# pokey-synth.net
KiCad netlist of a schematic drawn in EAGLE
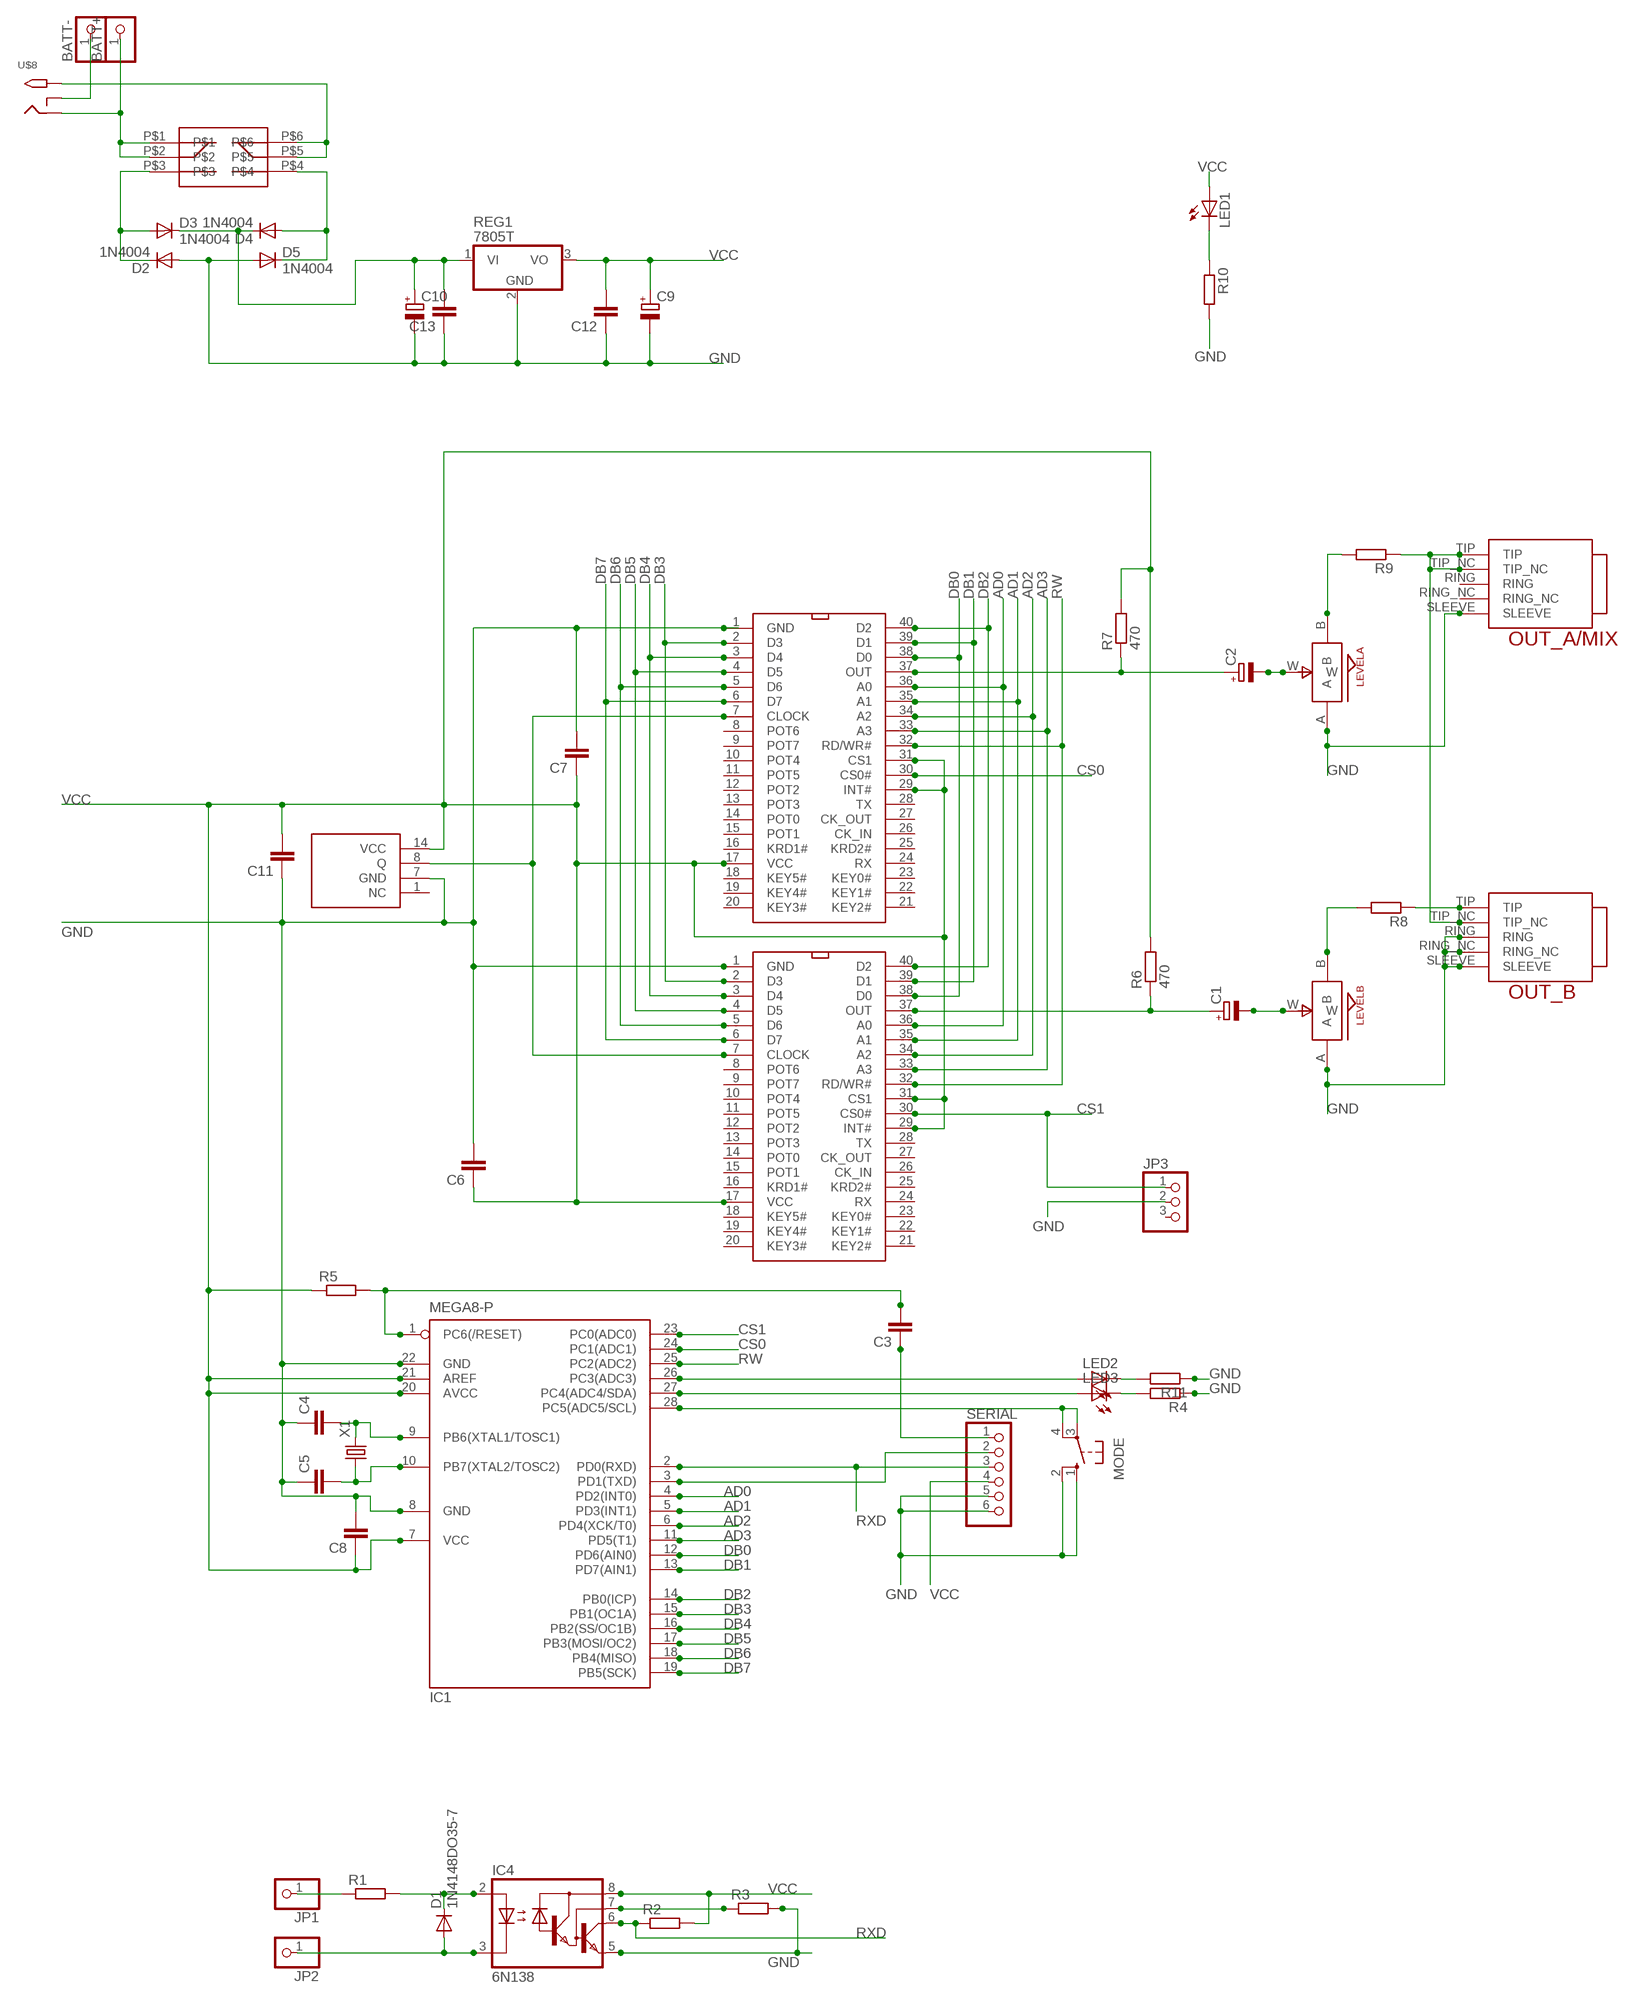
[diagram p0: schematic, sheet 1]

(export (version "E")
  (design (tool "Eeschema 10.0.6"))
  (components
    (comp (ref "BATT+")
      (value "PINHD-1X1")
      (footprint "eagle-import:1X01")
      (libsource (lib "eagle-import") (part "PINHD-1X1"))
    )
    (comp (ref "BATT-")
      (value "PINHD-1X1")
      (footprint "eagle-import:1X01")
      (libsource (lib "eagle-import") (part "PINHD-1X1"))
    )
    (comp (ref "C1")
      (value "CPOL-EUE2-5")
      (footprint "eagle-import:E2-5")
      (libsource (lib "eagle-import") (part "CPOL-EUE2-5"))
    )
    (comp (ref "C2")
      (value "CPOL-EUE2-5")
      (footprint "eagle-import:E2-5")
      (libsource (lib "eagle-import") (part "CPOL-EUE2-5"))
    )
    (comp (ref "C3")
      (value "C-EU025-024X044")
      (footprint "eagle-import:C025-024X044")
      (libsource (lib "eagle-import") (part "C-EU025-024X044"))
    )
    (comp (ref "C4")
      (value "C-EU025-024X044")
      (footprint "eagle-import:C025-024X044")
      (libsource (lib "eagle-import") (part "C-EU025-024X044"))
    )
    (comp (ref "C5")
      (value "C-EU025-024X044")
      (footprint "eagle-import:C025-024X044")
      (libsource (lib "eagle-import") (part "C-EU025-024X044"))
    )
    (comp (ref "C6")
      (value "C-EU025-024X044")
      (footprint "eagle-import:C025-024X044")
      (libsource (lib "eagle-import") (part "C-EU025-024X044"))
    )
    (comp (ref "C7")
      (value "C-EU025-024X044")
      (footprint "eagle-import:C025-024X044")
      (libsource (lib "eagle-import") (part "C-EU025-024X044"))
    )
    (comp (ref "C8")
      (value "C-EU025-024X044")
      (footprint "eagle-import:C025-024X044")
      (libsource (lib "eagle-import") (part "C-EU025-024X044"))
    )
    (comp (ref "C9")
      (value "CPOL-EUE2-5")
      (footprint "eagle-import:E2-5")
      (libsource (lib "eagle-import") (part "CPOL-EUE2-5"))
    )
    (comp (ref "C10")
      (value "CPOL-EUE2-5")
      (footprint "eagle-import:E2-5")
      (libsource (lib "eagle-import") (part "CPOL-EUE2-5"))
    )
    (comp (ref "C11")
      (value "C-EU025-024X044")
      (footprint "eagle-import:C025-024X044")
      (libsource (lib "eagle-import") (part "C-EU025-024X044"))
    )
    (comp (ref "C12")
      (value "C-EU025-024X044")
      (footprint "eagle-import:C025-024X044")
      (libsource (lib "eagle-import") (part "C-EU025-024X044"))
    )
    (comp (ref "C13")
      (value "C-EU025-024X044")
      (footprint "eagle-import:C025-024X044")
      (libsource (lib "eagle-import") (part "C-EU025-024X044"))
    )
    (comp (ref "D1")
      (value "1N4148DO35-7")
      (footprint "eagle-import:DO35-7")
      (libsource (lib "eagle-import") (part "1N4148DO35-7"))
    )
    (comp (ref "D2")
      (value "1N4004")
      (footprint "eagle-import:DO-VERT")
      (libsource (lib "eagle-import") (part "1N4004"))
    )
    (comp (ref "D3")
      (value "1N4004")
      (footprint "eagle-import:DO-VERT")
      (libsource (lib "eagle-import") (part "1N4004"))
    )
    (comp (ref "D4")
      (value "1N4004")
      (footprint "eagle-import:DO-VERT")
      (libsource (lib "eagle-import") (part "1N4004"))
    )
    (comp (ref "D5")
      (value "1N4004")
      (footprint "eagle-import:DO-VERT")
      (libsource (lib "eagle-import") (part "1N4004"))
    )
    (comp (ref "IC1")
      (value "MEGA8-P")
      (footprint "eagle-import:DIL28-3")
      (libsource (lib "eagle-import") (part "MEGA8-P"))
    )
    (comp (ref "IC2")
      (value "POKEYDIP40")
      (footprint "eagle-import:DIL40")
      (libsource (lib "eagle-import") (part "POKEYDIP40"))
    )
    (comp (ref "IC3")
      (value "POKEYDIP40")
      (footprint "eagle-import:DIL40")
      (libsource (lib "eagle-import") (part "POKEYDIP40"))
    )
    (comp (ref "IC4")
      (value "6N138")
      (footprint "eagle-import:DIL08")
      (fields (field (name "MF") "VISHAY/TELEFUNKEN"))
      (libsource (lib "eagle-import") (part "6N138"))
    )
    (comp (ref "JP1")
      (value "PINHD-1X1")
      (footprint "eagle-import:1X01")
      (libsource (lib "eagle-import") (part "PINHD-1X1"))
    )
    (comp (ref "JP2")
      (value "PINHD-1X1")
      (footprint "eagle-import:1X01")
      (libsource (lib "eagle-import") (part "PINHD-1X1"))
    )
    (comp (ref "JP3")
      (value "PINHD-1X3")
      (footprint "eagle-import:1X03")
      (libsource (lib "eagle-import") (part "PINHD-1X3"))
    )
    (comp (ref "LED1")
      (value "LED3MM")
      (footprint "eagle-import:LED3MM")
      (libsource (lib "eagle-import") (part "LED3MM"))
    )
    (comp (ref "LED2")
      (value "LED3MM")
      (footprint "eagle-import:LED3MM")
      (libsource (lib "eagle-import") (part "LED3MM"))
    )
    (comp (ref "LED3")
      (value "LED3MM")
      (footprint "eagle-import:LED3MM")
      (libsource (lib "eagle-import") (part "LED3MM"))
    )
    (comp (ref "LEVELA")
      (value "ALPS_POT_SMALL")
      (footprint "eagle-import:SMALL_ALPS_POT")
      (libsource (lib "eagle-import") (part "ALPS_POT_SMALL"))
    )
    (comp (ref "LEVELB")
      (value "ALPS_POT_SMALL")
      (footprint "eagle-import:SMALL_ALPS_POT")
      (libsource (lib "eagle-import") (part "ALPS_POT_SMALL"))
    )
    (comp (ref "MODE")
      (value "10-XX")
      (footprint "eagle-import:B3F-10XX")
      (fields (field (name "MPN") "B3F-1000"))
      (libsource (lib "eagle-import") (part "10-XX"))
    )
    (comp (ref "OSC1")
      (value "TTLOSC")
      (footprint "eagle-import:TTLOSC")
      (libsource (lib "eagle-import") (part "TTLOSC"))
    )
    (comp (ref "OUT_A/MIX")
      (value "TRUCONNECTJACK")
      (footprint "eagle-import:TRUCONNECTJACK")
      (libsource (lib "eagle-import") (part "TRUCONNECTJACK"))
    )
    (comp (ref "OUT_B")
      (value "TRUCONNECTJACK")
      (footprint "eagle-import:TRUCONNECTJACK")
      (libsource (lib "eagle-import") (part "TRUCONNECTJACK"))
    )
    (comp (ref "R1")
      (value "R-EU_0207/7")
      (footprint "eagle-import:0207_7")
      (libsource (lib "eagle-import") (part "R-EU_0207/7"))
    )
    (comp (ref "R2")
      (value "R-EU_0207/7")
      (footprint "eagle-import:0207_7")
      (libsource (lib "eagle-import") (part "R-EU_0207/7"))
    )
    (comp (ref "R3")
      (value "R-EU_0207/7")
      (footprint "eagle-import:0207_7")
      (libsource (lib "eagle-import") (part "R-EU_0207/7"))
    )
    (comp (ref "R4")
      (value "R-EU_0207/7")
      (footprint "eagle-import:0207_7")
      (libsource (lib "eagle-import") (part "R-EU_0207/7"))
    )
    (comp (ref "R5")
      (value "R-EU_0207/7")
      (footprint "eagle-import:0207_7")
      (libsource (lib "eagle-import") (part "R-EU_0207/7"))
    )
    (comp (ref "R6")
      (value "470")
      (footprint "eagle-import:0207_7")
      (libsource (lib "eagle-import") (part "R-EU_0207/7"))
    )
    (comp (ref "R7")
      (value "470")
      (footprint "eagle-import:0207_7")
      (libsource (lib "eagle-import") (part "R-EU_0207/7"))
    )
    (comp (ref "R8")
      (value "R-EU_0207/7")
      (footprint "eagle-import:0207_7")
      (libsource (lib "eagle-import") (part "R-EU_0207/7"))
    )
    (comp (ref "R9")
      (value "R-EU_0207/7")
      (footprint "eagle-import:0207_7")
      (libsource (lib "eagle-import") (part "R-EU_0207/7"))
    )
    (comp (ref "R10")
      (value "R-EU_0207/7")
      (footprint "eagle-import:0207_7")
      (libsource (lib "eagle-import") (part "R-EU_0207/7"))
    )
    (comp (ref "R11")
      (value "R-EU_0207/7")
      (footprint "eagle-import:0207_7")
      (libsource (lib "eagle-import") (part "R-EU_0207/7"))
    )
    (comp (ref "REG1")
      (value "7805T")
      (footprint "eagle-import:TO220H")
      (libsource (lib "eagle-import") (part "78T05"))
    )
    (comp (ref "SERIAL")
      (value "HEADER-1X6")
      (footprint "eagle-import:1X06_OVAL")
      (libsource (lib "eagle-import") (part "HEADER-1X6"))
    )
    (comp (ref "U$8")
      (value "2.1MMJACKTHM")
      (footprint "eagle-import:PJ-102A")
      (libsource (lib "eagle-import") (part "2.1MMJACKTHM"))
    )
    (comp (ref "U$9")
      (value "2P2T_LATCHING")
      (footprint "eagle-import:2P2T_LATCHING")
      (libsource (lib "eagle-import") (part "2P2T_LATCHING"))
    )
    (comp (ref "X1")
      (value "CRYSTALHC49U-V")
      (footprint "eagle-import:HC49U-V")
      (libsource (lib "eagle-import") (part "CRYSTALHC49U-V"))
    )
  )
  (nets
    (net (code "1") (name "/AD0") (class "Default")
      (node (ref "IC1") (pin "4") (pinfunction "PD2(INT0)_4") (pintype "bidirectional"))
      (node (ref "IC2") (pin "36") (pinfunction "A0_36") (pintype "input"))
      (node (ref "IC3") (pin "36") (pinfunction "A0_36") (pintype "input"))
    )
    (net (code "2") (name "/AD1") (class "Default")
      (node (ref "IC1") (pin "5") (pinfunction "PD3(INT1)_5") (pintype "bidirectional"))
      (node (ref "IC2") (pin "35") (pinfunction "A1_35") (pintype "input"))
      (node (ref "IC3") (pin "35") (pinfunction "A1_35") (pintype "input"))
    )
    (net (code "3") (name "/AD2") (class "Default")
      (node (ref "IC1") (pin "6") (pinfunction "PD4(XCK/T0)_6") (pintype "bidirectional"))
      (node (ref "IC2") (pin "34") (pinfunction "A2_34") (pintype "input"))
      (node (ref "IC3") (pin "34") (pinfunction "A2_34") (pintype "input"))
    )
    (net (code "4") (name "/AD3") (class "Default")
      (node (ref "IC1") (pin "11") (pinfunction "PD5(T1)_11") (pintype "bidirectional"))
      (node (ref "IC2") (pin "33") (pinfunction "A3_33") (pintype "input"))
      (node (ref "IC3") (pin "33") (pinfunction "A3_33") (pintype "input"))
    )
    (net (code "5") (name "/CS0") (class "Default")
      (node (ref "IC1") (pin "24") (pinfunction "PC1(ADC1)_24") (pintype "bidirectional"))
      (node (ref "IC2") (pin "30") (pinfunction "CS0#_30") (pintype "input"))
    )
    (net (code "6") (name "/CS1") (class "Default")
      (node (ref "IC1") (pin "23") (pinfunction "PC0(ADC0)_23") (pintype "bidirectional"))
      (node (ref "IC3") (pin "30") (pinfunction "CS0#_30") (pintype "input"))
      (node (ref "JP3") (pin "1") (pinfunction "1_1") (pintype "passive"))
    )
    (net (code "7") (name "/DB0") (class "Default")
      (node (ref "IC1") (pin "12") (pinfunction "PD6(AIN0)_12") (pintype "bidirectional"))
      (node (ref "IC2") (pin "38") (pinfunction "D0_38") (pintype "bidirectional"))
      (node (ref "IC3") (pin "38") (pinfunction "D0_38") (pintype "bidirectional"))
    )
    (net (code "8") (name "/DB1") (class "Default")
      (node (ref "IC1") (pin "13") (pinfunction "PD7(AIN1)_13") (pintype "bidirectional"))
      (node (ref "IC2") (pin "39") (pinfunction "D1_39") (pintype "bidirectional"))
      (node (ref "IC3") (pin "39") (pinfunction "D1_39") (pintype "bidirectional"))
    )
    (net (code "9") (name "/DB2") (class "Default")
      (node (ref "IC1") (pin "14") (pinfunction "PB0(ICP)_14") (pintype "bidirectional"))
      (node (ref "IC2") (pin "40") (pinfunction "D2_40") (pintype "bidirectional"))
      (node (ref "IC3") (pin "40") (pinfunction "D2_40") (pintype "bidirectional"))
    )
    (net (code "10") (name "/DB3") (class "Default")
      (node (ref "IC1") (pin "15") (pinfunction "PB1(OC1A)_15") (pintype "bidirectional"))
      (node (ref "IC2") (pin "2") (pinfunction "D3_2") (pintype "bidirectional"))
      (node (ref "IC3") (pin "2") (pinfunction "D3_2") (pintype "bidirectional"))
    )
    (net (code "11") (name "/DB4") (class "Default")
      (node (ref "IC1") (pin "16") (pinfunction "PB2(SS/OC1B)_16") (pintype "bidirectional"))
      (node (ref "IC2") (pin "3") (pinfunction "D4_3") (pintype "bidirectional"))
      (node (ref "IC3") (pin "3") (pinfunction "D4_3") (pintype "bidirectional"))
    )
    (net (code "12") (name "/DB5") (class "Default")
      (node (ref "IC1") (pin "17") (pinfunction "PB3(MOSI/OC2)_17") (pintype "bidirectional"))
      (node (ref "IC2") (pin "4") (pinfunction "D5_4") (pintype "bidirectional"))
      (node (ref "IC3") (pin "4") (pinfunction "D5_4") (pintype "bidirectional"))
    )
    (net (code "13") (name "/DB6") (class "Default")
      (node (ref "IC1") (pin "18") (pinfunction "PB4(MISO)_18") (pintype "bidirectional"))
      (node (ref "IC2") (pin "5") (pinfunction "D6_5") (pintype "bidirectional"))
      (node (ref "IC3") (pin "5") (pinfunction "D6_5") (pintype "bidirectional"))
    )
    (net (code "14") (name "/DB7") (class "Default")
      (node (ref "IC1") (pin "19") (pinfunction "PB5(SCK)_19") (pintype "bidirectional"))
      (node (ref "IC2") (pin "6") (pinfunction "D7_6") (pintype "bidirectional"))
      (node (ref "IC3") (pin "6") (pinfunction "D7_6") (pintype "bidirectional"))
    )
    (net (code "15") (name "/GND") (class "Default")
      (node (ref "C10") (pin "-") (pinfunction "-_-") (pintype "passive"))
      (node (ref "C11") (pin "1") (pinfunction "1_1") (pintype "passive"))
      (node (ref "C12") (pin "1") (pinfunction "1_1") (pintype "passive"))
      (node (ref "C13") (pin "1") (pinfunction "1_1") (pintype "passive"))
      (node (ref "C4") (pin "1") (pinfunction "1_1") (pintype "passive"))
      (node (ref "C5") (pin "1") (pinfunction "1_1") (pintype "passive"))
      (node (ref "C6") (pin "2") (pinfunction "2_2") (pintype "passive"))
      (node (ref "C7") (pin "2") (pinfunction "2_2") (pintype "passive"))
      (node (ref "C8") (pin "2") (pinfunction "2_2") (pintype "passive"))
      (node (ref "C9") (pin "-") (pinfunction "-_-") (pintype "passive"))
      (node (ref "D2") (pin "A") (pinfunction "A_A") (pintype "passive"))
      (node (ref "D5") (pin "A") (pinfunction "A_A") (pintype "passive"))
      (node (ref "IC1") (pin "22") (pinfunction "GND_22") (pintype "power_in"))
      (node (ref "IC1") (pin "8") (pinfunction "GND_8") (pintype "power_in"))
      (node (ref "IC2") (pin "1") (pinfunction "GND_1") (pintype "power_in"))
      (node (ref "IC3") (pin "1") (pinfunction "GND_1") (pintype "power_in"))
      (node (ref "IC4") (pin "5") (pinfunction "GND_5") (pintype "passive"))
      (node (ref "JP3") (pin "2") (pinfunction "2_2") (pintype "passive"))
      (node (ref "LEVELA") (pin "A") (pinfunction "A_A") (pintype "bidirectional"))
      (node (ref "LEVELB") (pin "A") (pinfunction "A_A") (pintype "bidirectional"))
      (node (ref "MODE") (pin "1") (pinfunction "S_1") (pintype "passive"))
      (node (ref "MODE") (pin "2") (pinfunction "S1_2") (pintype "passive"))
      (node (ref "OSC1") (pin "7") (pinfunction "GND_7") (pintype "bidirectional"))
      (node (ref "OUT_A/MIX") (pin "SLEEVE") (pinfunction "SLEEVE_SLEEVE") (pintype "bidirectional"))
      (node (ref "OUT_B") (pin "RING") (pinfunction "RING_RING") (pintype "bidirectional"))
      (node (ref "OUT_B") (pin "RING_NC") (pinfunction "RING_NC_RING_NC") (pintype "bidirectional"))
      (node (ref "OUT_B") (pin "SLEEVE") (pinfunction "SLEEVE_SLEEVE") (pintype "bidirectional"))
      (node (ref "R10") (pin "2") (pinfunction "2_2") (pintype "passive"))
      (node (ref "R11") (pin "1") (pinfunction "1_1") (pintype "passive"))
      (node (ref "R3") (pin "2") (pinfunction "2_2") (pintype "passive"))
      (node (ref "R4") (pin "1") (pinfunction "1_1") (pintype "passive"))
      (node (ref "REG1") (pin "2") (pinfunction "GND_2") (pintype "passive"))
      (node (ref "SERIAL") (pin "5") (pinfunction "5_5") (pintype "passive"))
      (node (ref "SERIAL") (pin "6") (pinfunction "6_6") (pintype "passive"))
    )
    (net (code "16") (name "/RW") (class "Default")
      (node (ref "IC1") (pin "25") (pinfunction "PC2(ADC2)_25") (pintype "bidirectional"))
      (node (ref "IC2") (pin "32") (pinfunction "RD/WR#_32") (pintype "input"))
      (node (ref "IC3") (pin "32") (pinfunction "RD/WR#_32") (pintype "input"))
    )
    (net (code "17") (name "/RXD") (class "Default")
      (node (ref "IC1") (pin "2") (pinfunction "PD0(RXD)_2") (pintype "bidirectional"))
      (node (ref "IC4") (pin "6") (pinfunction "VO_6") (pintype "passive"))
      (node (ref "R2") (pin "1") (pinfunction "1_1") (pintype "passive"))
      (node (ref "SERIAL") (pin "3") (pinfunction "3_3") (pintype "passive"))
    )
    (net (code "18") (name "/VCC") (class "Default")
      (node (ref "C11") (pin "2") (pinfunction "2_2") (pintype "passive"))
      (node (ref "C12") (pin "2") (pinfunction "2_2") (pintype "passive"))
      (node (ref "C6") (pin "1") (pinfunction "1_1") (pintype "passive"))
      (node (ref "C7") (pin "1") (pinfunction "1_1") (pintype "passive"))
      (node (ref "C8") (pin "1") (pinfunction "1_1") (pintype "passive"))
      (node (ref "C9") (pin "+") (pinfunction "+_+") (pintype "passive"))
      (node (ref "IC1") (pin "20") (pinfunction "AVCC_20") (pintype "power_in"))
      (node (ref "IC1") (pin "21") (pinfunction "AREF_21") (pintype "passive"))
      (node (ref "IC1") (pin "7") (pinfunction "VCC_7") (pintype "power_in"))
      (node (ref "IC2") (pin "17") (pinfunction "VCC_17") (pintype "power_in"))
      (node (ref "IC2") (pin "29") (pinfunction "INT#_29") (pintype "bidirectional"))
      (node (ref "IC2") (pin "31") (pinfunction "CS1_31") (pintype "input"))
      (node (ref "IC3") (pin "17") (pinfunction "VCC_17") (pintype "power_in"))
      (node (ref "IC3") (pin "29") (pinfunction "INT#_29") (pintype "bidirectional"))
      (node (ref "IC3") (pin "31") (pinfunction "CS1_31") (pintype "input"))
      (node (ref "IC4") (pin "8") (pinfunction "VCC_8") (pintype "passive"))
      (node (ref "LED1") (pin "A") (pinfunction "A_A") (pintype "passive"))
      (node (ref "OSC1") (pin "14") (pinfunction "VCC_14") (pintype "bidirectional"))
      (node (ref "R2") (pin "2") (pinfunction "2_2") (pintype "passive"))
      (node (ref "R5") (pin "1") (pinfunction "1_1") (pintype "passive"))
      (node (ref "R6") (pin "2") (pinfunction "2_2") (pintype "passive"))
      (node (ref "R7") (pin "2") (pinfunction "2_2") (pintype "passive"))
      (node (ref "REG1") (pin "3") (pinfunction "VO_3") (pintype "passive"))
      (node (ref "SERIAL") (pin "4") (pinfunction "4_4") (pintype "passive"))
    )
    (net (code "19") (name "Net-(BATT+-Pad1)") (class "Default")
      (node (ref "BATT+") (pin "1") (pinfunction "1_1") (pintype "passive"))
      (node (ref "U$8") (pin "RING") (pinfunction "RING_RING") (pintype "bidirectional"))
      (node (ref "U$9") (pin "P$1") (pinfunction "P$1_P$1") (pintype "bidirectional"))
      (node (ref "U$9") (pin "P$2") (pinfunction "P$2_P$2") (pintype "bidirectional"))
    )
    (net (code "20") (name "Net-(BATT--Pad1)") (class "Default")
      (node (ref "BATT-") (pin "1") (pinfunction "1_1") (pintype "passive"))
      (node (ref "U$8") (pin "RING_SW") (pinfunction "RING_SW_RING_SW") (pintype "bidirectional"))
    )
    (net (code "21") (name "Net-(C1-Pad-)") (class "Default")
      (node (ref "C1") (pin "-") (pinfunction "-_-") (pintype "passive"))
      (node (ref "LEVELB") (pin "W") (pinfunction "W_W") (pintype "bidirectional"))
    )
    (net (code "22") (name "Net-(C2-Pad-)") (class "Default")
      (node (ref "C2") (pin "-") (pinfunction "-_-") (pintype "passive"))
      (node (ref "LEVELA") (pin "W") (pinfunction "W_W") (pintype "bidirectional"))
    )
    (net (code "23") (name "Net-(C3-Pad1)") (class "Default")
      (node (ref "C3") (pin "1") (pinfunction "1_1") (pintype "passive"))
      (node (ref "SERIAL") (pin "1") (pinfunction "1_1") (pintype "passive"))
    )
    (net (code "24") (name "Net-(D2-PadC)") (class "Default")
      (node (ref "D2") (pin "C") (pinfunction "C_C") (pintype "passive"))
      (node (ref "D3") (pin "A") (pinfunction "A_A") (pintype "passive"))
      (node (ref "U$9") (pin "P$3") (pinfunction "P$3_P$3") (pintype "bidirectional"))
    )
    (net (code "25") (name "Net-(D4-PadA)") (class "Default")
      (node (ref "D4") (pin "A") (pinfunction "A_A") (pintype "passive"))
      (node (ref "D5") (pin "C") (pinfunction "C_C") (pintype "passive"))
      (node (ref "U$9") (pin "P$4") (pinfunction "P$4_P$4") (pintype "bidirectional"))
    )
    (net (code "26") (name "Net-(IC1-PB6(XTAL1{slash}TOSC1))") (class "Default")
      (node (ref "C4") (pin "2") (pinfunction "2_2") (pintype "passive"))
      (node (ref "IC1") (pin "9") (pinfunction "PB6(XTAL1/TOSC1)_9") (pintype "bidirectional"))
      (node (ref "X1") (pin "2") (pinfunction "2_2") (pintype "passive"))
    )
    (net (code "27") (name "Net-(IC1-PB7(XTAL2{slash}TOSC2))") (class "Default")
      (node (ref "C5") (pin "2") (pinfunction "2_2") (pintype "passive"))
      (node (ref "IC1") (pin "10") (pinfunction "PB7(XTAL2/TOSC2)_10") (pintype "bidirectional"))
      (node (ref "X1") (pin "1") (pinfunction "1_1") (pintype "passive"))
    )
    (net (code "28") (name "Net-(IC1-PC3(ADC3))") (class "Default")
      (node (ref "IC1") (pin "26") (pinfunction "PC3(ADC3)_26") (pintype "bidirectional"))
      (node (ref "LED2") (pin "A") (pinfunction "A_A") (pintype "passive"))
    )
    (net (code "29") (name "Net-(IC1-PC4(ADC4{slash}SDA))") (class "Default")
      (node (ref "IC1") (pin "27") (pinfunction "PC4(ADC4/SDA)_27") (pintype "bidirectional"))
      (node (ref "LED3") (pin "A") (pinfunction "A_A") (pintype "passive"))
    )
    (net (code "30") (name "Net-(IC1-PC5(ADC5{slash}SCL))") (class "Default")
      (node (ref "IC1") (pin "28") (pinfunction "PC5(ADC5/SCL)_28") (pintype "bidirectional"))
      (node (ref "MODE") (pin "3") (pinfunction "P_3") (pintype "passive"))
      (node (ref "MODE") (pin "4") (pinfunction "P1_4") (pintype "passive"))
    )
    (net (code "31") (name "Net-(IC1-PC6({slash}RESET))") (class "Default")
      (node (ref "C3") (pin "2") (pinfunction "2_2") (pintype "passive"))
      (node (ref "IC1") (pin "1") (pinfunction "PC6(/RESET)_1") (pintype "bidirectional"))
      (node (ref "R5") (pin "2") (pinfunction "2_2") (pintype "passive"))
    )
    (net (code "32") (name "Net-(IC1-PD1(TXD))") (class "Default")
      (node (ref "IC1") (pin "3") (pinfunction "PD1(TXD)_3") (pintype "bidirectional"))
      (node (ref "SERIAL") (pin "2") (pinfunction "2_2") (pintype "passive"))
    )
    (net (code "33") (name "Net-(IC2-CLOCK)") (class "Default")
      (node (ref "IC2") (pin "7") (pinfunction "CLOCK_7") (pintype "input"))
      (node (ref "IC3") (pin "7") (pinfunction "CLOCK_7") (pintype "input"))
      (node (ref "OSC1") (pin "8") (pinfunction "Q_8") (pintype "bidirectional"))
    )
    (net (code "34") (name "Net-(IC2-OUT)") (class "Default")
      (node (ref "C2") (pin "+") (pinfunction "+_+") (pintype "passive"))
      (node (ref "IC2") (pin "37") (pinfunction "OUT_37") (pintype "output"))
      (node (ref "R7") (pin "1") (pinfunction "1_1") (pintype "passive"))
    )
    (net (code "35") (name "Net-(IC3-OUT)") (class "Default")
      (node (ref "C1") (pin "+") (pinfunction "+_+") (pintype "passive"))
      (node (ref "IC3") (pin "37") (pinfunction "OUT_37") (pintype "output"))
      (node (ref "R6") (pin "1") (pinfunction "1_1") (pintype "passive"))
    )
    (net (code "36") (name "Net-(IC4-A)") (class "Default")
      (node (ref "D1") (pin "C") (pinfunction "C_C") (pintype "passive"))
      (node (ref "IC4") (pin "2") (pinfunction "A_2") (pintype "passive"))
      (node (ref "R1") (pin "2") (pinfunction "2_2") (pintype "passive"))
    )
    (net (code "37") (name "Net-(IC4-C)") (class "Default")
      (node (ref "D1") (pin "A") (pinfunction "A_A") (pintype "passive"))
      (node (ref "IC4") (pin "3") (pinfunction "C_3") (pintype "passive"))
      (node (ref "JP2") (pin "1") (pinfunction "1_1") (pintype "passive"))
    )
    (net (code "38") (name "Net-(IC4-VB)") (class "Default")
      (node (ref "IC4") (pin "7") (pinfunction "VB_7") (pintype "passive"))
      (node (ref "R3") (pin "1") (pinfunction "1_1") (pintype "passive"))
    )
    (net (code "39") (name "Net-(JP1-Pad1)") (class "Default")
      (node (ref "JP1") (pin "1") (pinfunction "1_1") (pintype "passive"))
      (node (ref "R1") (pin "1") (pinfunction "1_1") (pintype "passive"))
    )
    (net (code "40") (name "Net-(LED1-C)") (class "Default")
      (node (ref "LED1") (pin "K") (pinfunction "C_K") (pintype "passive"))
      (node (ref "R10") (pin "1") (pinfunction "1_1") (pintype "passive"))
    )
    (net (code "41") (name "Net-(LED2-C)") (class "Default")
      (node (ref "LED2") (pin "K") (pinfunction "C_K") (pintype "passive"))
      (node (ref "R11") (pin "2") (pinfunction "2_2") (pintype "passive"))
    )
    (net (code "42") (name "Net-(LED3-C)") (class "Default")
      (node (ref "LED3") (pin "K") (pinfunction "C_K") (pintype "passive"))
      (node (ref "R4") (pin "2") (pinfunction "2_2") (pintype "passive"))
    )
    (net (code "43") (name "Net-(LEVELA-PadB)") (class "Default")
      (node (ref "LEVELA") (pin "B") (pinfunction "B_B") (pintype "bidirectional"))
      (node (ref "R9") (pin "2") (pinfunction "2_2") (pintype "passive"))
    )
    (net (code "44") (name "Net-(LEVELB-PadB)") (class "Default")
      (node (ref "LEVELB") (pin "B") (pinfunction "B_B") (pintype "bidirectional"))
      (node (ref "R8") (pin "2") (pinfunction "2_2") (pintype "passive"))
    )
    (net (code "45") (name "Net-(OUT_A/MIX-PadTIP)") (class "Default")
      (node (ref "OUT_A/MIX") (pin "TIP") (pinfunction "TIP_TIP") (pintype "bidirectional"))
      (node (ref "OUT_A/MIX") (pin "TIP_NC") (pinfunction "TIP_NC_TIP_NC") (pintype "bidirectional"))
      (node (ref "OUT_B") (pin "TIP_NC") (pinfunction "TIP_NC_TIP_NC") (pintype "bidirectional"))
      (node (ref "R9") (pin "1") (pinfunction "1_1") (pintype "passive"))
    )
    (net (code "46") (name "Net-(OUT_B-PadTIP)") (class "Default")
      (node (ref "OUT_B") (pin "TIP") (pinfunction "TIP_TIP") (pintype "bidirectional"))
      (node (ref "R8") (pin "1") (pinfunction "1_1") (pintype "passive"))
    )
    (net (code "47") (name "Net-(REG1-VI)") (class "Default")
      (node (ref "C10") (pin "+") (pinfunction "+_+") (pintype "passive"))
      (node (ref "C13") (pin "2") (pinfunction "2_2") (pintype "passive"))
      (node (ref "D3") (pin "C") (pinfunction "C_C") (pintype "passive"))
      (node (ref "D4") (pin "C") (pinfunction "C_C") (pintype "passive"))
      (node (ref "REG1") (pin "1") (pinfunction "VI_1") (pintype "input"))
    )
    (net (code "48") (name "Net-(U$8-PadTIP)") (class "Default")
      (node (ref "U$8") (pin "TIP") (pinfunction "TIP_TIP") (pintype "bidirectional"))
      (node (ref "U$9") (pin "P$5") (pinfunction "P$5_P$5") (pintype "bidirectional"))
      (node (ref "U$9") (pin "P$6") (pinfunction "P$6_P$6") (pintype "bidirectional"))
    )
    (net (code "49") (name "unconnected-(IC2-CK_IN-Pad26)") (class "Default")
      (node (ref "IC2") (pin "26") (pinfunction "CK_IN_26") (pintype "input"))
    )
    (net (code "50") (name "unconnected-(IC2-CK_OUT-Pad27)") (class "Default")
      (node (ref "IC2") (pin "27") (pinfunction "CK_OUT_27") (pintype "output"))
    )
    (net (code "51") (name "unconnected-(IC2-KEY0#-Pad23)") (class "Default")
      (node (ref "IC2") (pin "23") (pinfunction "KEY0#_23") (pintype "bidirectional"))
    )
    (net (code "52") (name "unconnected-(IC2-KEY1#-Pad22)") (class "Default")
      (node (ref "IC2") (pin "22") (pinfunction "KEY1#_22") (pintype "bidirectional"))
    )
    (net (code "53") (name "unconnected-(IC2-KEY2#-Pad21)") (class "Default")
      (node (ref "IC2") (pin "21") (pinfunction "KEY2#_21") (pintype "bidirectional"))
    )
    (net (code "54") (name "unconnected-(IC2-KEY3#-Pad20)") (class "Default")
      (node (ref "IC2") (pin "20") (pinfunction "KEY3#_20") (pintype "bidirectional"))
    )
    (net (code "55") (name "unconnected-(IC2-KEY4#-Pad19)") (class "Default")
      (node (ref "IC2") (pin "19") (pinfunction "KEY4#_19") (pintype "bidirectional"))
    )
    (net (code "56") (name "unconnected-(IC2-KEY5#-Pad18)") (class "Default")
      (node (ref "IC2") (pin "18") (pinfunction "KEY5#_18") (pintype "bidirectional"))
    )
    (net (code "57") (name "unconnected-(IC2-KRD1#-Pad16)") (class "Default")
      (node (ref "IC2") (pin "16") (pinfunction "KRD1#_16") (pintype "bidirectional"))
    )
    (net (code "58") (name "unconnected-(IC2-KRD2#-Pad25)") (class "Default")
      (node (ref "IC2") (pin "25") (pinfunction "KRD2#_25") (pintype "bidirectional"))
    )
    (net (code "59") (name "unconnected-(IC2-POT0-Pad14)") (class "Default")
      (node (ref "IC2") (pin "14") (pinfunction "POT0_14") (pintype "input"))
    )
    (net (code "60") (name "unconnected-(IC2-POT1-Pad15)") (class "Default")
      (node (ref "IC2") (pin "15") (pinfunction "POT1_15") (pintype "input"))
    )
    (net (code "61") (name "unconnected-(IC2-POT2-Pad12)") (class "Default")
      (node (ref "IC2") (pin "12") (pinfunction "POT2_12") (pintype "input"))
    )
    (net (code "62") (name "unconnected-(IC2-POT3-Pad13)") (class "Default")
      (node (ref "IC2") (pin "13") (pinfunction "POT3_13") (pintype "input"))
    )
    (net (code "63") (name "unconnected-(IC2-POT4-Pad10)") (class "Default")
      (node (ref "IC2") (pin "10") (pinfunction "POT4_10") (pintype "input"))
    )
    (net (code "64") (name "unconnected-(IC2-POT5-Pad11)") (class "Default")
      (node (ref "IC2") (pin "11") (pinfunction "POT5_11") (pintype "input"))
    )
    (net (code "65") (name "unconnected-(IC2-POT6-Pad8)") (class "Default")
      (node (ref "IC2") (pin "8") (pinfunction "POT6_8") (pintype "input"))
    )
    (net (code "66") (name "unconnected-(IC2-POT7-Pad9)") (class "Default")
      (node (ref "IC2") (pin "9") (pinfunction "POT7_9") (pintype "input"))
    )
    (net (code "67") (name "unconnected-(IC2-RX-Pad24)") (class "Default")
      (node (ref "IC2") (pin "24") (pinfunction "RX_24") (pintype "input"))
    )
    (net (code "68") (name "unconnected-(IC2-TX-Pad28)") (class "Default")
      (node (ref "IC2") (pin "28") (pinfunction "TX_28") (pintype "output"))
    )
    (net (code "69") (name "unconnected-(IC3-CK_IN-Pad26)") (class "Default")
      (node (ref "IC3") (pin "26") (pinfunction "CK_IN_26") (pintype "input"))
    )
    (net (code "70") (name "unconnected-(IC3-CK_OUT-Pad27)") (class "Default")
      (node (ref "IC3") (pin "27") (pinfunction "CK_OUT_27") (pintype "output"))
    )
    (net (code "71") (name "unconnected-(IC3-KEY0#-Pad23)") (class "Default")
      (node (ref "IC3") (pin "23") (pinfunction "KEY0#_23") (pintype "bidirectional"))
    )
    (net (code "72") (name "unconnected-(IC3-KEY1#-Pad22)") (class "Default")
      (node (ref "IC3") (pin "22") (pinfunction "KEY1#_22") (pintype "bidirectional"))
    )
    (net (code "73") (name "unconnected-(IC3-KEY2#-Pad21)") (class "Default")
      (node (ref "IC3") (pin "21") (pinfunction "KEY2#_21") (pintype "bidirectional"))
    )
    (net (code "74") (name "unconnected-(IC3-KEY3#-Pad20)") (class "Default")
      (node (ref "IC3") (pin "20") (pinfunction "KEY3#_20") (pintype "bidirectional"))
    )
    (net (code "75") (name "unconnected-(IC3-KEY4#-Pad19)") (class "Default")
      (node (ref "IC3") (pin "19") (pinfunction "KEY4#_19") (pintype "bidirectional"))
    )
    (net (code "76") (name "unconnected-(IC3-KEY5#-Pad18)") (class "Default")
      (node (ref "IC3") (pin "18") (pinfunction "KEY5#_18") (pintype "bidirectional"))
    )
    (net (code "77") (name "unconnected-(IC3-KRD1#-Pad16)") (class "Default")
      (node (ref "IC3") (pin "16") (pinfunction "KRD1#_16") (pintype "bidirectional"))
    )
    (net (code "78") (name "unconnected-(IC3-KRD2#-Pad25)") (class "Default")
      (node (ref "IC3") (pin "25") (pinfunction "KRD2#_25") (pintype "bidirectional"))
    )
    (net (code "79") (name "unconnected-(IC3-POT0-Pad14)") (class "Default")
      (node (ref "IC3") (pin "14") (pinfunction "POT0_14") (pintype "input"))
    )
    (net (code "80") (name "unconnected-(IC3-POT1-Pad15)") (class "Default")
      (node (ref "IC3") (pin "15") (pinfunction "POT1_15") (pintype "input"))
    )
    (net (code "81") (name "unconnected-(IC3-POT2-Pad12)") (class "Default")
      (node (ref "IC3") (pin "12") (pinfunction "POT2_12") (pintype "input"))
    )
    (net (code "82") (name "unconnected-(IC3-POT3-Pad13)") (class "Default")
      (node (ref "IC3") (pin "13") (pinfunction "POT3_13") (pintype "input"))
    )
    (net (code "83") (name "unconnected-(IC3-POT4-Pad10)") (class "Default")
      (node (ref "IC3") (pin "10") (pinfunction "POT4_10") (pintype "input"))
    )
    (net (code "84") (name "unconnected-(IC3-POT5-Pad11)") (class "Default")
      (node (ref "IC3") (pin "11") (pinfunction "POT5_11") (pintype "input"))
    )
    (net (code "85") (name "unconnected-(IC3-POT6-Pad8)") (class "Default")
      (node (ref "IC3") (pin "8") (pinfunction "POT6_8") (pintype "input"))
    )
    (net (code "86") (name "unconnected-(IC3-POT7-Pad9)") (class "Default")
      (node (ref "IC3") (pin "9") (pinfunction "POT7_9") (pintype "input"))
    )
    (net (code "87") (name "unconnected-(IC3-RX-Pad24)") (class "Default")
      (node (ref "IC3") (pin "24") (pinfunction "RX_24") (pintype "input"))
    )
    (net (code "88") (name "unconnected-(IC3-TX-Pad28)") (class "Default")
      (node (ref "IC3") (pin "28") (pinfunction "TX_28") (pintype "output"))
    )
    (net (code "89") (name "unconnected-(JP3-Pad3)") (class "Default")
      (node (ref "JP3") (pin "3") (pinfunction "3_3") (pintype "passive"))
    )
    (net (code "90") (name "unconnected-(OSC1-NC-Pad1)") (class "Default")
      (node (ref "OSC1") (pin "1") (pinfunction "NC_1") (pintype "bidirectional"))
    )
    (net (code "91") (name "unconnected-(OUT_A/MIX-PadRING)") (class "Default")
      (node (ref "OUT_A/MIX") (pin "RING") (pinfunction "RING_RING") (pintype "bidirectional"))
    )
    (net (code "92") (name "unconnected-(OUT_A/MIX-PadRING_NC)") (class "Default")
      (node (ref "OUT_A/MIX") (pin "RING_NC") (pinfunction "RING_NC_RING_NC") (pintype "bidirectional"))
    )
  )
)
